# Peripherals.net
KiCad netlist of a schematic drawn in EAGLE
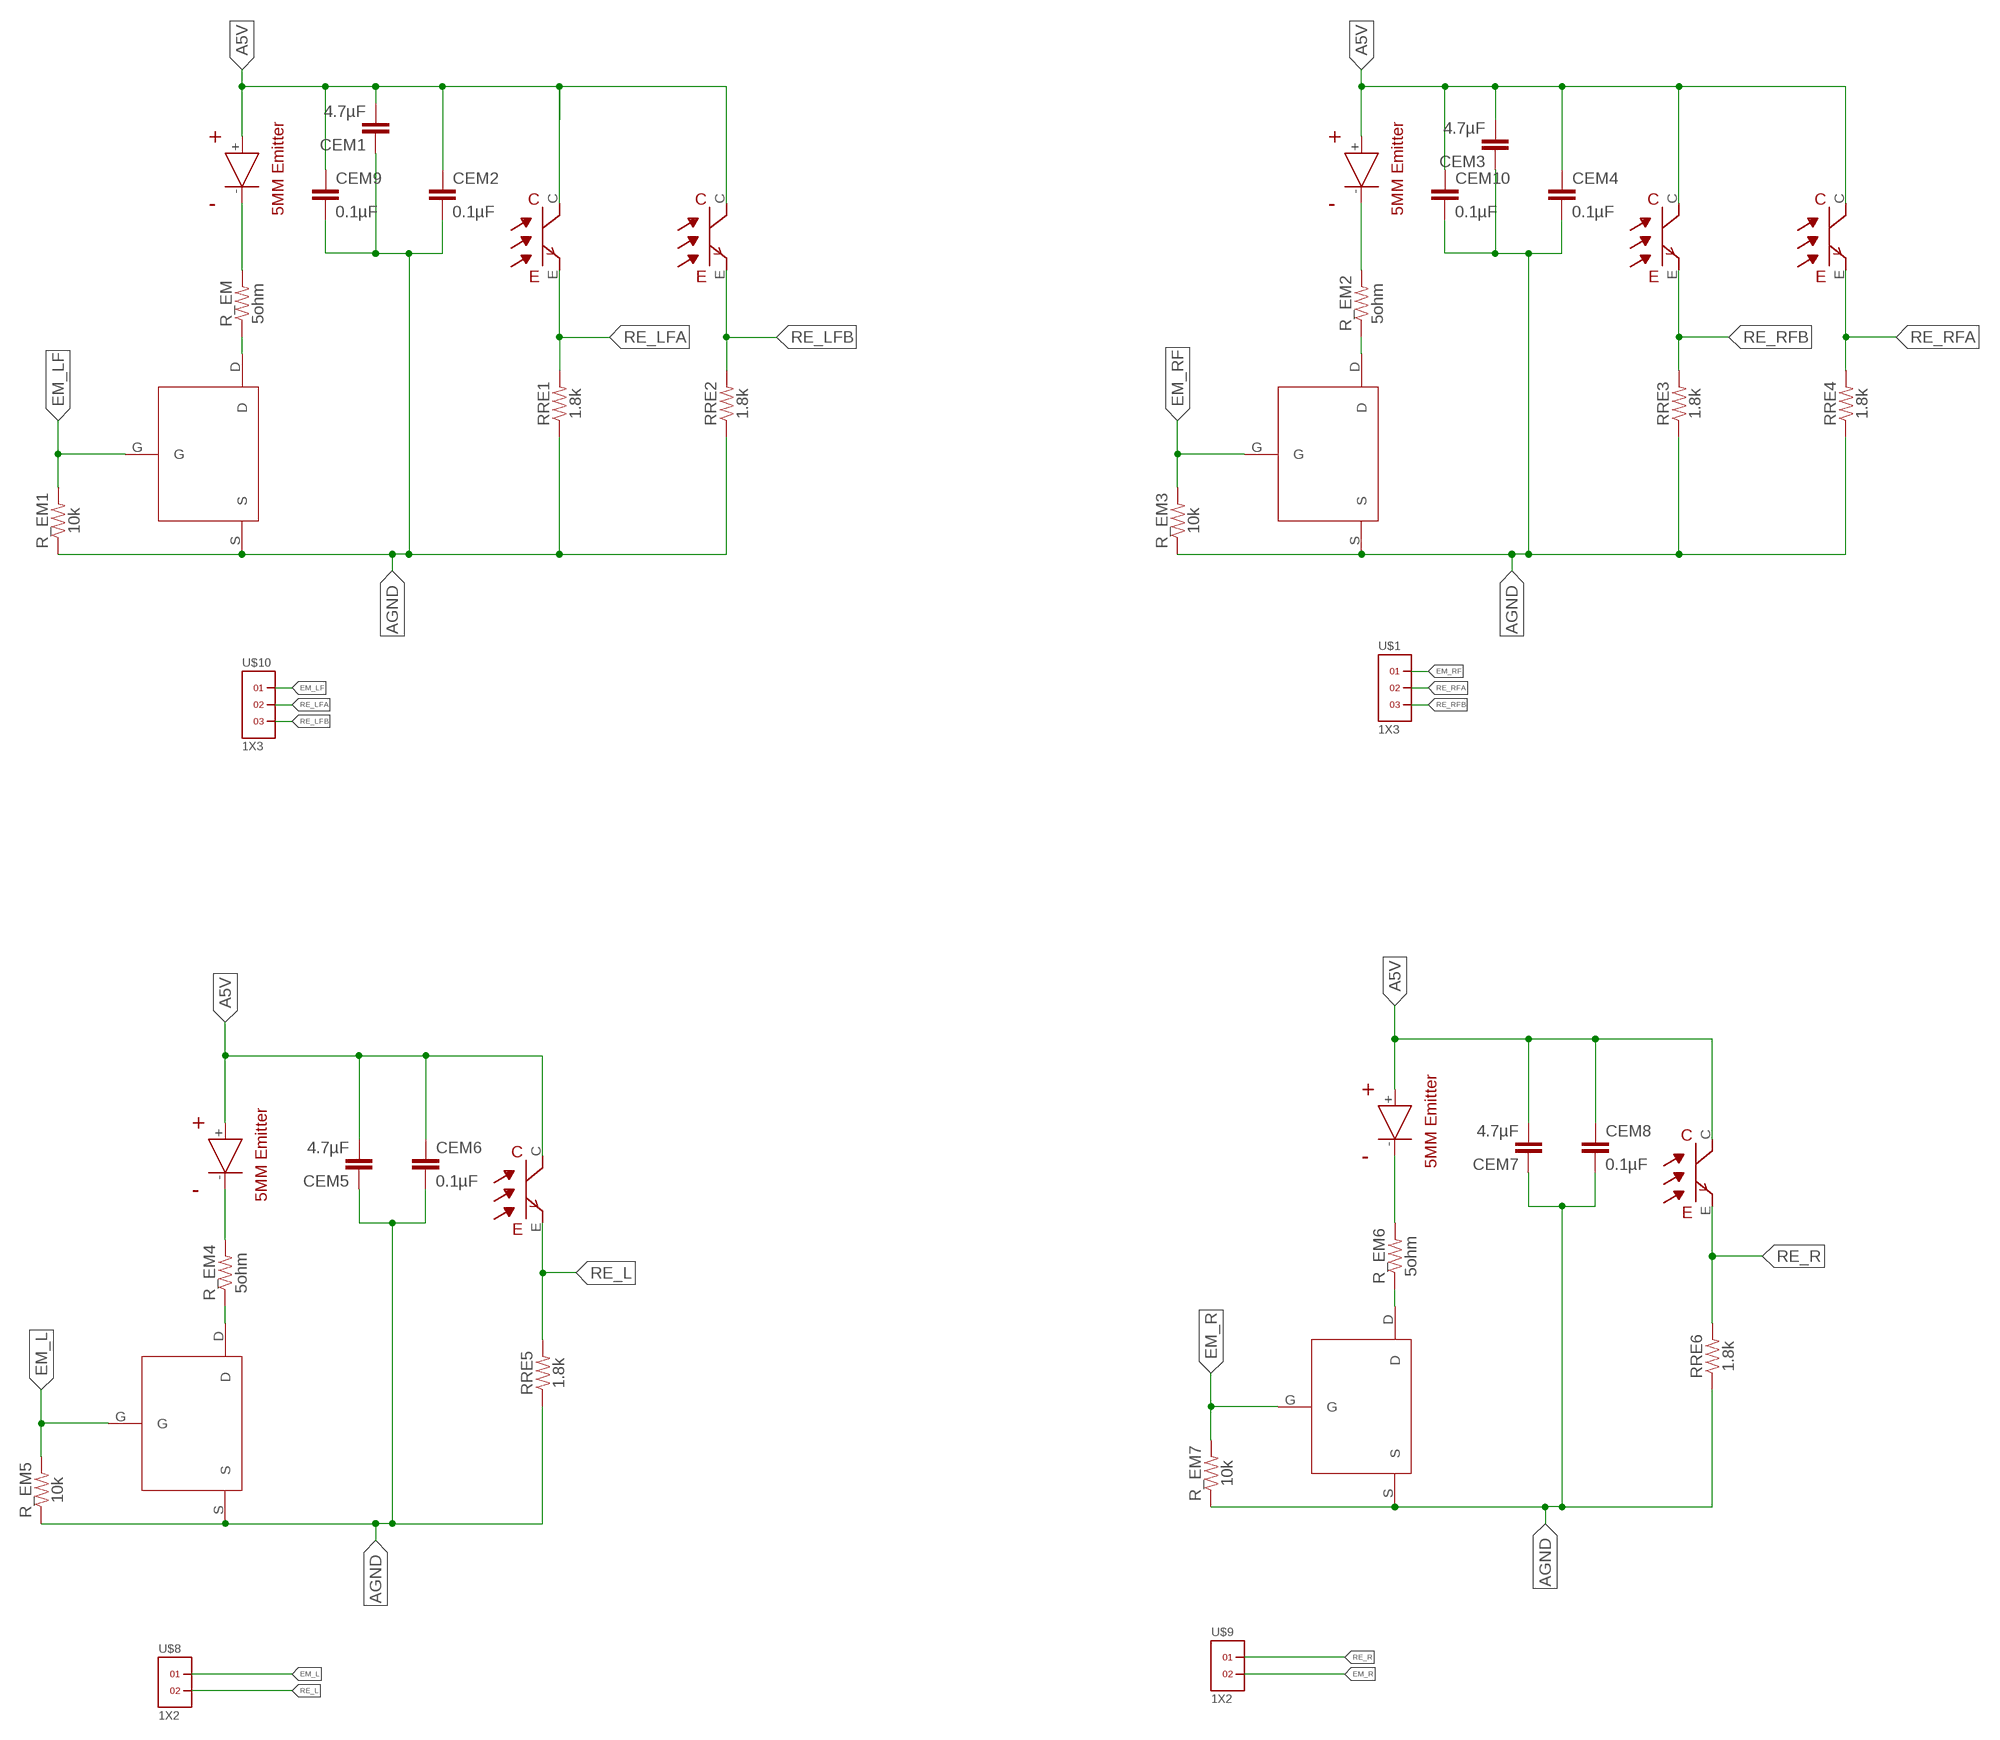
[diagram p0: schematic, sheet 1, part 1 of 2]
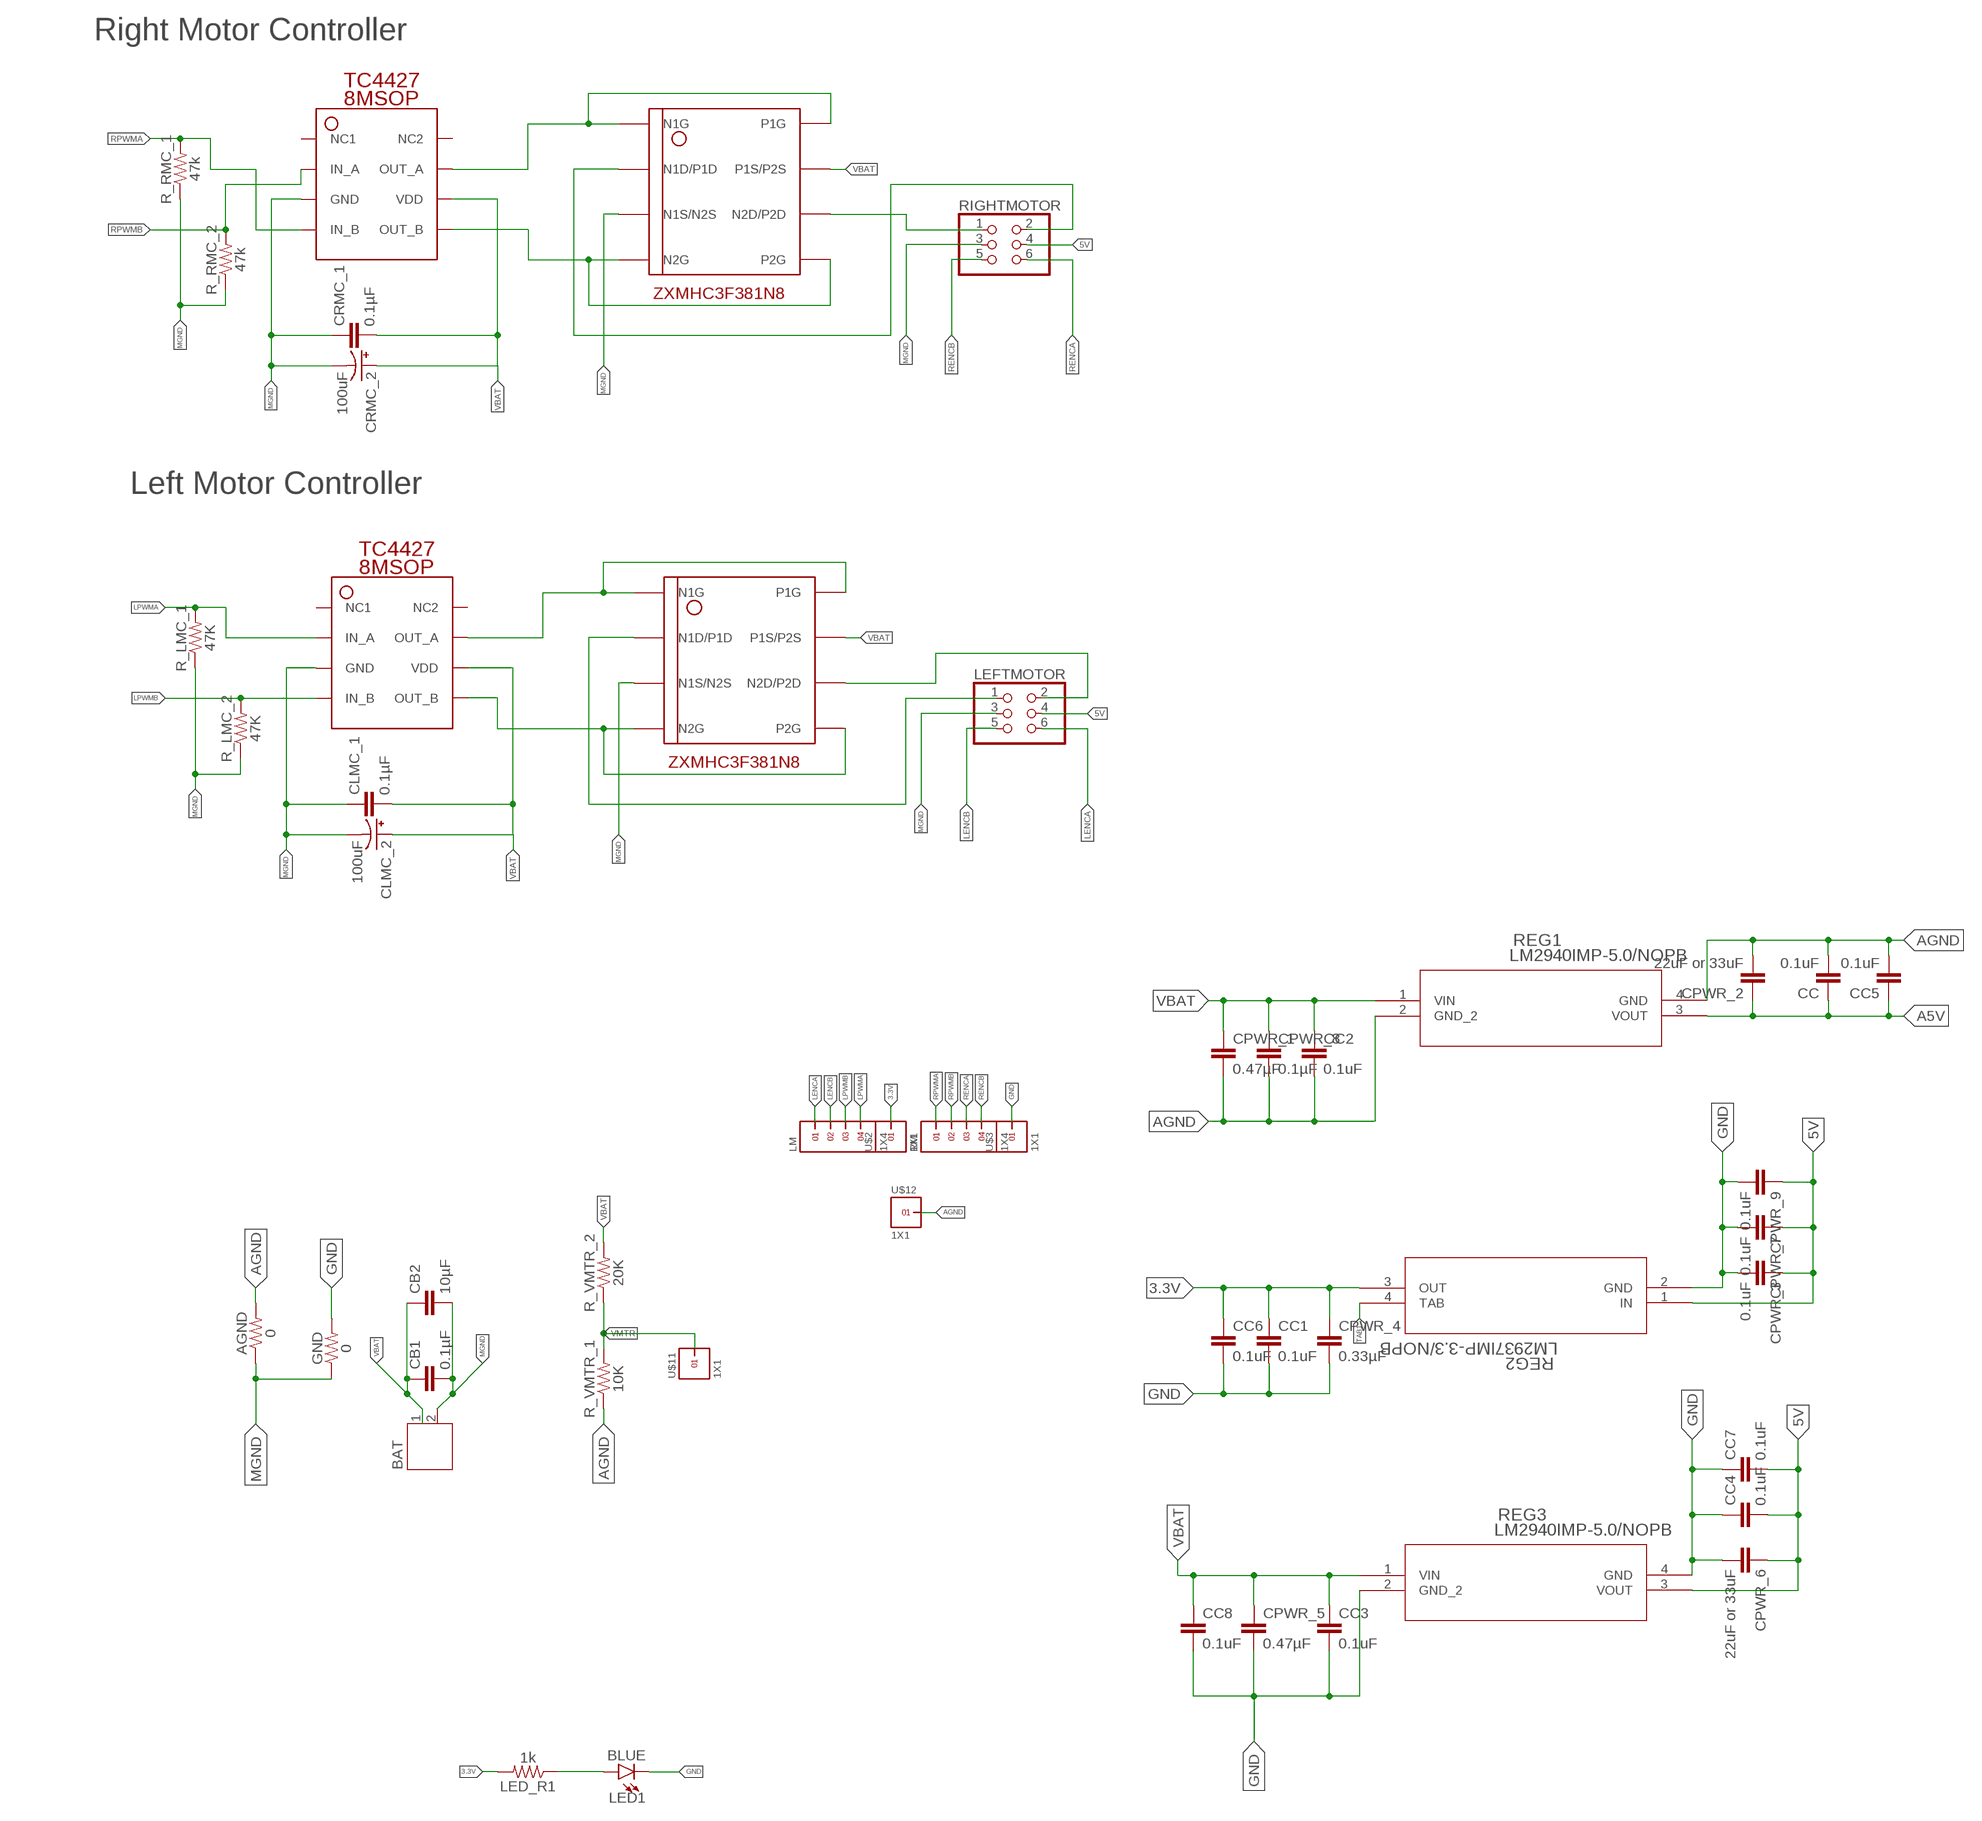
[diagram p1: schematic, sheet 1, part 2 of 2]

(export (version "E")
  (design (tool "Eeschema 10.0.6"))
  (components
    (comp (ref "AGND")
      (value "0")
      (footprint "eagle-import:0805")
      (libsource (lib "eagle-import") (part "SparkFun-Resistors_532_0.75OHM-0805-1/4W-1%"))
    )
    (comp (ref "BAT")
      (value "JST-PH2")
      (footprint "eagle-import:JST-PH2")
      (libsource (lib "eagle-import") (part "JST-PH2"))
    )
    (comp (ref "CB1")
      (value "0.1µF")
      (footprint "eagle-import:0805")
      (libsource (lib "eagle-import") (part "SparkFun-Capacitors_510_0.33UF/330NF-0805-50V-10%"))
    )
    (comp (ref "CB2")
      (value "10µF")
      (footprint "eagle-import:0805")
      (libsource (lib "eagle-import") (part "SparkFun-Capacitors_510_0.33UF/330NF-0805-50V-10%"))
    )
    (comp (ref "CC")
      (value "0.1uF")
      (footprint "eagle-import:0805")
      (libsource (lib "eagle-import") (part "0.33UF/330NF-0805-50V-10%"))
    )
    (comp (ref "CC1")
      (value "0.1uF")
      (footprint "eagle-import:0805")
      (libsource (lib "eagle-import") (part "0.33UF/330NF-0805-50V-10%"))
    )
    (comp (ref "CC2")
      (value "0.1uF")
      (footprint "eagle-import:0805")
      (libsource (lib "eagle-import") (part "0.33UF/330NF-0805-50V-10%"))
    )
    (comp (ref "CC3")
      (value "0.1uF")
      (footprint "eagle-import:0805")
      (libsource (lib "eagle-import") (part "0.33UF/330NF-0805-50V-10%"))
    )
    (comp (ref "CC4")
      (value "0.1uF")
      (footprint "eagle-import:0805")
      (libsource (lib "eagle-import") (part "0.33UF/330NF-0805-50V-10%"))
    )
    (comp (ref "CC5")
      (value "0.1uF")
      (footprint "eagle-import:0805")
      (libsource (lib "eagle-import") (part "0.33UF/330NF-0805-50V-10%"))
    )
    (comp (ref "CC6")
      (value "0.1uF")
      (footprint "eagle-import:0805")
      (libsource (lib "eagle-import") (part "0.33UF/330NF-0805-50V-10%"))
    )
    (comp (ref "CC7")
      (value "0.1uF")
      (footprint "eagle-import:0805")
      (libsource (lib "eagle-import") (part "0.33UF/330NF-0805-50V-10%"))
    )
    (comp (ref "CC8")
      (value "0.1uF")
      (footprint "eagle-import:0805")
      (libsource (lib "eagle-import") (part "0.33UF/330NF-0805-50V-10%"))
    )
    (comp (ref "CEM1")
      (value "4.7µF")
      (footprint "eagle-import:0805")
      (libsource (lib "eagle-import") (part "0.33UF/330NF-0805-50V-10%"))
    )
    (comp (ref "CEM2")
      (value "0.1µF")
      (footprint "eagle-import:0805")
      (libsource (lib "eagle-import") (part "0.33UF/330NF-0805-50V-10%"))
    )
    (comp (ref "CEM3")
      (value "4.7µF")
      (footprint "eagle-import:0805")
      (libsource (lib "eagle-import") (part "0.33UF/330NF-0805-50V-10%"))
    )
    (comp (ref "CEM4")
      (value "0.1µF")
      (footprint "eagle-import:0805")
      (libsource (lib "eagle-import") (part "0.33UF/330NF-0805-50V-10%"))
    )
    (comp (ref "CEM5")
      (value "4.7µF")
      (footprint "eagle-import:0805")
      (libsource (lib "eagle-import") (part "0.33UF/330NF-0805-50V-10%"))
    )
    (comp (ref "CEM6")
      (value "0.1µF")
      (footprint "eagle-import:0805")
      (libsource (lib "eagle-import") (part "0.33UF/330NF-0805-50V-10%"))
    )
    (comp (ref "CEM7")
      (value "4.7µF")
      (footprint "eagle-import:0805")
      (libsource (lib "eagle-import") (part "0.33UF/330NF-0805-50V-10%"))
    )
    (comp (ref "CEM8")
      (value "0.1µF")
      (footprint "eagle-import:0805")
      (libsource (lib "eagle-import") (part "0.33UF/330NF-0805-50V-10%"))
    )
    (comp (ref "CEM9")
      (value "0.1µF")
      (footprint "eagle-import:0805")
      (libsource (lib "eagle-import") (part "0.33UF/330NF-0805-50V-10%"))
    )
    (comp (ref "CEM10")
      (value "0.1µF")
      (footprint "eagle-import:0805")
      (libsource (lib "eagle-import") (part "0.33UF/330NF-0805-50V-10%"))
    )
    (comp (ref "CLMC_1")
      (value "0.1µF")
      (footprint "eagle-import:0805")
      (libsource (lib "eagle-import") (part "SparkFun-Capacitors_510_0.33UF/330NF-0805-50V-10%"))
    )
    (comp (ref "CLMC_2")
      (value "100uF")
      (footprint "eagle-import:EIA7343")
      (libsource (lib "eagle-import") (part "100UF-POLAR-EIA7343-10V-10%(TANT)"))
    )
    (comp (ref "CPWR_1")
      (value "0.47µF")
      (footprint "eagle-import:0805")
      (libsource (lib "eagle-import") (part "0.33UF/330NF-0805-50V-10%"))
    )
    (comp (ref "CPWR_2")
      (value "22uF or 33uF")
      (footprint "eagle-import:0805")
      (libsource (lib "eagle-import") (part "0.33UF/330NF-0805-50V-10%"))
    )
    (comp (ref "CPWR_3")
      (value "0.1uF")
      (footprint "eagle-import:0805")
      (libsource (lib "eagle-import") (part "0.33UF/330NF-0805-50V-10%"))
    )
    (comp (ref "CPWR_4")
      (value "0.33µF")
      (footprint "eagle-import:0805")
      (libsource (lib "eagle-import") (part "0.33UF/330NF-0805-50V-10%"))
    )
    (comp (ref "CPWR_5")
      (value "0.47µF")
      (footprint "eagle-import:0805")
      (libsource (lib "eagle-import") (part "0.33UF/330NF-0805-50V-10%"))
    )
    (comp (ref "CPWR_6")
      (value "22uF or 33uF")
      (footprint "eagle-import:0805")
      (libsource (lib "eagle-import") (part "0.33UF/330NF-0805-50V-10%"))
    )
    (comp (ref "CPWR_7")
      (value "0.1uF")
      (footprint "eagle-import:0805")
      (libsource (lib "eagle-import") (part "0.33UF/330NF-0805-50V-10%"))
    )
    (comp (ref "CPWR_8")
      (value "0.1µF")
      (footprint "eagle-import:0805")
      (libsource (lib "eagle-import") (part "0.33UF/330NF-0805-50V-10%"))
    )
    (comp (ref "CPWR_9")
      (value "0.1uF")
      (footprint "eagle-import:0805")
      (libsource (lib "eagle-import") (part "0.33UF/330NF-0805-50V-10%"))
    )
    (comp (ref "CRMC_1")
      (value "0.1µF")
      (footprint "eagle-import:0805")
      (libsource (lib "eagle-import") (part "SparkFun-Capacitors_510_0.33UF/330NF-0805-50V-10%"))
    )
    (comp (ref "CRMC_2")
      (value "100uF")
      (footprint "eagle-import:EIA7343")
      (libsource (lib "eagle-import") (part "100UF-POLAR-EIA7343-10V-10%(TANT)"))
    )
    (comp (ref "EM_L")
      (value "EMITTER")
      (footprint "eagle-import:EMITTER")
      (libsource (lib "eagle-import") (part "EMITTER"))
    )
    (comp (ref "EM_LF")
      (value "EMITTER")
      (footprint "eagle-import:EMITTER")
      (libsource (lib "eagle-import") (part "EMITTER"))
    )
    (comp (ref "EM_R")
      (value "EMITTER")
      (footprint "eagle-import:EMITTER")
      (libsource (lib "eagle-import") (part "EMITTER"))
    )
    (comp (ref "EM_RF")
      (value "EMITTER")
      (footprint "eagle-import:EMITTER")
      (libsource (lib "eagle-import") (part "EMITTER"))
    )
    (comp (ref "GND")
      (value "0")
      (footprint "eagle-import:0805")
      (libsource (lib "eagle-import") (part "SparkFun-Resistors_532_0.75OHM-0805-1/4W-1%"))
    )
    (comp (ref "LED1")
      (value "BLUE")
      (footprint "eagle-import:LED-1206")
      (libsource (lib "eagle-import") (part "LED-BLUE1206"))
    )
    (comp (ref "LED_R1")
      (value "1k")
      (footprint "eagle-import:0805")
      (libsource (lib "eagle-import") (part "0.75OHM-0805-1/4W-1%"))
    )
    (comp (ref "LEFTMOTOR")
      (value "PINHD-2X3")
      (footprint "eagle-import:2X03")
      (libsource (lib "eagle-import") (part "PINHD-2X3"))
    )
    (comp (ref "LM")
      (value "1X4")
      (footprint "eagle-import:1X4")
      (libsource (lib "eagle-import") (part "1X4"))
    )
    (comp (ref "REG1")
      (value "LM2940IMP-5.0/NOPB")
      (footprint "eagle-import:MP04A")
      (fields
        (field (name "MANUFACTURER_PART_NUMBER") "LM2940IMP5.0NOPB")
        (field (name "COPYRIGHT") "Copyright C 2015 Accelerated Designs. All rights reserved")
      )
      (libsource (lib "eagle-import") (part "LM2940IMP-5.0/NOPB"))
    )
    (comp (ref "REG2")
      (value "LM2937IMP-3.3/NOPB")
      (footprint "eagle-import:MP04A")
      (fields
        (field (name "MANUFACTURER_PART_NUMBER") "lm2937imp3_3nopb")
        (field (name "COPYRIGHT") "Copyright C 2015 Accelerated Designs. All rights reserved")
      )
      (libsource (lib "eagle-import") (part "LM2937IMP-3.3/NOPB"))
    )
    (comp (ref "REG3")
      (value "LM2940IMP-5.0/NOPB")
      (footprint "eagle-import:MP04A")
      (fields
        (field (name "MANUFACTURER_PART_NUMBER") "LM2940IMP5.0NOPB")
        (field (name "COPYRIGHT") "Copyright C 2015 Accelerated Designs. All rights reserved")
      )
      (libsource (lib "eagle-import") (part "LM2940IMP-5.0/NOPB"))
    )
    (comp (ref "RE_L")
      (value "RECEIVER")
      (footprint "eagle-import:RECEIVER")
      (libsource (lib "eagle-import") (part "RECEIVER"))
    )
    (comp (ref "RE_LFA")
      (value "RECEIVER")
      (footprint "eagle-import:RECEIVER")
      (libsource (lib "eagle-import") (part "RECEIVER"))
    )
    (comp (ref "RE_LFB")
      (value "RECEIVER")
      (footprint "eagle-import:RECEIVER")
      (libsource (lib "eagle-import") (part "RECEIVER"))
    )
    (comp (ref "RE_R")
      (value "RECEIVER")
      (footprint "eagle-import:RECEIVER")
      (libsource (lib "eagle-import") (part "RECEIVER"))
    )
    (comp (ref "RE_RFA")
      (value "RECEIVER")
      (footprint "eagle-import:RECEIVER")
      (libsource (lib "eagle-import") (part "RECEIVER"))
    )
    (comp (ref "RE_RFB")
      (value "RECEIVER")
      (footprint "eagle-import:RECEIVER")
      (libsource (lib "eagle-import") (part "RECEIVER"))
    )
    (comp (ref "RIGHTMOTOR")
      (value "PINHD-2X3")
      (footprint "eagle-import:2X03")
      (libsource (lib "eagle-import") (part "PINHD-2X3"))
    )
    (comp (ref "RM")
      (value "1X4")
      (footprint "eagle-import:1X4")
      (libsource (lib "eagle-import") (part "1X4"))
    )
    (comp (ref "RRE1")
      (value "1.8k")
      (footprint "eagle-import:0805")
      (libsource (lib "eagle-import") (part "0.75OHM-0805-1/4W-1%"))
    )
    (comp (ref "RRE2")
      (value "1.8k")
      (footprint "eagle-import:0805")
      (libsource (lib "eagle-import") (part "0.75OHM-0805-1/4W-1%"))
    )
    (comp (ref "RRE3")
      (value "1.8k")
      (footprint "eagle-import:0805")
      (libsource (lib "eagle-import") (part "0.75OHM-0805-1/4W-1%"))
    )
    (comp (ref "RRE4")
      (value "1.8k")
      (footprint "eagle-import:0805")
      (libsource (lib "eagle-import") (part "0.75OHM-0805-1/4W-1%"))
    )
    (comp (ref "RRE5")
      (value "1.8k")
      (footprint "eagle-import:0805")
      (libsource (lib "eagle-import") (part "0.75OHM-0805-1/4W-1%"))
    )
    (comp (ref "RRE6")
      (value "1.8k")
      (footprint "eagle-import:0805")
      (libsource (lib "eagle-import") (part "0.75OHM-0805-1/4W-1%"))
    )
    (comp (ref "R_EM")
      (value "5ohm")
      (footprint "eagle-import:0805")
      (libsource (lib "eagle-import") (part "0.75OHM-0805-1/4W-1%"))
    )
    (comp (ref "R_EM1")
      (value "10k")
      (footprint "eagle-import:0805")
      (libsource (lib "eagle-import") (part "0.75OHM-0805-1/4W-1%"))
    )
    (comp (ref "R_EM2")
      (value "5ohm")
      (footprint "eagle-import:0805")
      (libsource (lib "eagle-import") (part "0.75OHM-0805-1/4W-1%"))
    )
    (comp (ref "R_EM3")
      (value "10k")
      (footprint "eagle-import:0805")
      (libsource (lib "eagle-import") (part "0.75OHM-0805-1/4W-1%"))
    )
    (comp (ref "R_EM4")
      (value "5ohm")
      (footprint "eagle-import:0805")
      (libsource (lib "eagle-import") (part "0.75OHM-0805-1/4W-1%"))
    )
    (comp (ref "R_EM5")
      (value "10k")
      (footprint "eagle-import:0805")
      (libsource (lib "eagle-import") (part "0.75OHM-0805-1/4W-1%"))
    )
    (comp (ref "R_EM6")
      (value "5ohm")
      (footprint "eagle-import:0805")
      (libsource (lib "eagle-import") (part "0.75OHM-0805-1/4W-1%"))
    )
    (comp (ref "R_EM7")
      (value "10k")
      (footprint "eagle-import:0805")
      (libsource (lib "eagle-import") (part "0.75OHM-0805-1/4W-1%"))
    )
    (comp (ref "R_LMC_1")
      (value "47K")
      (footprint "eagle-import:0805")
      (libsource (lib "eagle-import") (part "SparkFun-Resistors_532_0.75OHM-0805-1/4W-1%"))
    )
    (comp (ref "R_LMC_2")
      (value "47K")
      (footprint "eagle-import:0805")
      (libsource (lib "eagle-import") (part "SparkFun-Resistors_532_0.75OHM-0805-1/4W-1%"))
    )
    (comp (ref "R_RMC_1")
      (value "47k")
      (footprint "eagle-import:0805")
      (libsource (lib "eagle-import") (part "SparkFun-Resistors_532_0.75OHM-0805-1/4W-1%"))
    )
    (comp (ref "R_RMC_2")
      (value "47k")
      (footprint "eagle-import:0805")
      (libsource (lib "eagle-import") (part "SparkFun-Resistors_532_0.75OHM-0805-1/4W-1%"))
    )
    (comp (ref "R_VMTR_1")
      (value "10K")
      (footprint "eagle-import:0805")
      (libsource (lib "eagle-import") (part "0.75OHM-0805-1/4W-1%"))
    )
    (comp (ref "R_VMTR_2")
      (value "20K")
      (footprint "eagle-import:0805")
      (libsource (lib "eagle-import") (part "0.75OHM-0805-1/4W-1%"))
    )
    (comp (ref "U$1")
      (value "1X3")
      (footprint "eagle-import:1X3")
      (libsource (lib "eagle-import") (part "1X3"))
    )
    (comp (ref "U$2")
      (value "1X1")
      (footprint "eagle-import:1X1")
      (libsource (lib "eagle-import") (part "1X1"))
    )
    (comp (ref "U$3")
      (value "1X1")
      (footprint "eagle-import:1X1")
      (libsource (lib "eagle-import") (part "1X1"))
    )
    (comp (ref "U$4")
      (value "MCH3474")
      (footprint "eagle-import:MCH3474")
      (libsource (lib "eagle-import") (part "MCH3474"))
    )
    (comp (ref "U$5")
      (value "MCH3474")
      (footprint "eagle-import:MCH3474")
      (libsource (lib "eagle-import") (part "MCH3474"))
    )
    (comp (ref "U$6")
      (value "MCH3474")
      (footprint "eagle-import:MCH3474")
      (libsource (lib "eagle-import") (part "MCH3474"))
    )
    (comp (ref "U$7")
      (value "MCH3474")
      (footprint "eagle-import:MCH3474")
      (libsource (lib "eagle-import") (part "MCH3474"))
    )
    (comp (ref "U$8")
      (value "1X2")
      (footprint "eagle-import:1X2")
      (libsource (lib "eagle-import") (part "1X2"))
    )
    (comp (ref "U$9")
      (value "1X2")
      (footprint "eagle-import:1X2")
      (libsource (lib "eagle-import") (part "1X2"))
    )
    (comp (ref "U$10")
      (value "1X3")
      (footprint "eagle-import:1X3")
      (libsource (lib "eagle-import") (part "1X3"))
    )
    (comp (ref "U$11")
      (value "1X1")
      (footprint "eagle-import:1X1")
      (libsource (lib "eagle-import") (part "1X1"))
    )
    (comp (ref "U$12")
      (value "1X1")
      (footprint "eagle-import:1X1")
      (libsource (lib "eagle-import") (part "1X1"))
    )
    (comp (ref "U$15")
      (value "TC4427(8MSOP)")
      (footprint "eagle-import:TC4427(8MSOP)")
      (libsource (lib "eagle-import") (part "TC4427(8MSOP)"))
    )
    (comp (ref "U$16")
      (value "ZXMHC3F381N8")
      (footprint "eagle-import:ZXMHC3F381N8")
      (libsource (lib "eagle-import") (part "ZXMHC3F381N8"))
    )
    (comp (ref "U$17")
      (value "TC4427(8MSOP)")
      (footprint "eagle-import:TC4427(8MSOP)")
      (libsource (lib "eagle-import") (part "TC4427(8MSOP)"))
    )
    (comp (ref "U$18")
      (value "ZXMHC3F381N8")
      (footprint "eagle-import:ZXMHC3F381N8")
      (libsource (lib "eagle-import") (part "ZXMHC3F381N8"))
    )
  )
  (nets
    (net (code "1") (name "3.3V") (class "Default")
      (node (ref "CC1") (pin "1") (pinfunction "1_1") (pintype "passive"))
      (node (ref "CC6") (pin "1") (pinfunction "1_1") (pintype "passive"))
      (node (ref "CPWR_4") (pin "1") (pinfunction "1_1") (pintype "passive"))
      (node (ref "LED_R1") (pin "2") (pinfunction "2_2") (pintype "passive"))
      (node (ref "REG2") (pin "3") (pinfunction "OUT_3") (pintype "power_in"))
      (node (ref "U$2") (pin "1") (pinfunction "1_1") (pintype "bidirectional"))
    )
    (net (code "2") (name "5V") (class "Default")
      (node (ref "CC4") (pin "2") (pinfunction "2_2") (pintype "passive"))
      (node (ref "CC7") (pin "2") (pinfunction "2_2") (pintype "passive"))
      (node (ref "CPWR_3") (pin "1") (pinfunction "1_1") (pintype "passive"))
      (node (ref "CPWR_6") (pin "1") (pinfunction "1_1") (pintype "passive"))
      (node (ref "CPWR_7") (pin "1") (pinfunction "1_1") (pintype "passive"))
      (node (ref "CPWR_9") (pin "1") (pinfunction "1_1") (pintype "passive"))
      (node (ref "LEFTMOTOR") (pin "4") (pinfunction "4_4") (pintype "passive"))
      (node (ref "REG2") (pin "1") (pinfunction "IN_1") (pintype "power_in"))
      (node (ref "REG3") (pin "3") (pinfunction "VOUT_3") (pintype "output"))
      (node (ref "RIGHTMOTOR") (pin "4") (pinfunction "4_4") (pintype "passive"))
    )
    (net (code "3") (name "A5V") (class "Default")
      (node (ref "CC") (pin "1") (pinfunction "1_1") (pintype "passive"))
      (node (ref "CC5") (pin "1") (pinfunction "1_1") (pintype "passive"))
      (node (ref "CEM1") (pin "2") (pinfunction "2_2") (pintype "passive"))
      (node (ref "CEM10") (pin "1") (pinfunction "1_1") (pintype "passive"))
      (node (ref "CEM2") (pin "1") (pinfunction "1_1") (pintype "passive"))
      (node (ref "CEM3") (pin "2") (pinfunction "2_2") (pintype "passive"))
      (node (ref "CEM4") (pin "1") (pinfunction "1_1") (pintype "passive"))
      (node (ref "CEM5") (pin "2") (pinfunction "2_2") (pintype "passive"))
      (node (ref "CEM6") (pin "1") (pinfunction "1_1") (pintype "passive"))
      (node (ref "CEM7") (pin "2") (pinfunction "2_2") (pintype "passive"))
      (node (ref "CEM8") (pin "1") (pinfunction "1_1") (pintype "passive"))
      (node (ref "CEM9") (pin "1") (pinfunction "1_1") (pintype "passive"))
      (node (ref "CPWR_2") (pin "1") (pinfunction "1_1") (pintype "passive"))
      (node (ref "EM_L") (pin "+") (pinfunction "+_+") (pintype "bidirectional"))
      (node (ref "EM_LF") (pin "+") (pinfunction "+_+") (pintype "bidirectional"))
      (node (ref "EM_R") (pin "+") (pinfunction "+_+") (pintype "bidirectional"))
      (node (ref "EM_RF") (pin "+") (pinfunction "+_+") (pintype "bidirectional"))
      (node (ref "REG1") (pin "3") (pinfunction "VOUT_3") (pintype "output"))
      (node (ref "RE_L") (pin "C") (pinfunction "C_C") (pintype "bidirectional"))
      (node (ref "RE_LFA") (pin "C") (pinfunction "C_C") (pintype "bidirectional"))
      (node (ref "RE_LFB") (pin "C") (pinfunction "C_C") (pintype "bidirectional"))
      (node (ref "RE_R") (pin "C") (pinfunction "C_C") (pintype "bidirectional"))
      (node (ref "RE_RFA") (pin "C") (pinfunction "C_C") (pintype "bidirectional"))
      (node (ref "RE_RFB") (pin "C") (pinfunction "C_C") (pintype "bidirectional"))
    )
    (net (code "4") (name "AGND") (class "Default")
      (node (ref "AGND") (pin "2") (pinfunction "2_2") (pintype "passive"))
      (node (ref "CC") (pin "2") (pinfunction "2_2") (pintype "passive"))
      (node (ref "CC2") (pin "2") (pinfunction "2_2") (pintype "passive"))
      (node (ref "CC5") (pin "2") (pinfunction "2_2") (pintype "passive"))
      (node (ref "CEM1") (pin "1") (pinfunction "1_1") (pintype "passive"))
      (node (ref "CEM10") (pin "2") (pinfunction "2_2") (pintype "passive"))
      (node (ref "CEM2") (pin "2") (pinfunction "2_2") (pintype "passive"))
      (node (ref "CEM3") (pin "1") (pinfunction "1_1") (pintype "passive"))
      (node (ref "CEM4") (pin "2") (pinfunction "2_2") (pintype "passive"))
      (node (ref "CEM5") (pin "1") (pinfunction "1_1") (pintype "passive"))
      (node (ref "CEM6") (pin "2") (pinfunction "2_2") (pintype "passive"))
      (node (ref "CEM7") (pin "1") (pinfunction "1_1") (pintype "passive"))
      (node (ref "CEM8") (pin "2") (pinfunction "2_2") (pintype "passive"))
      (node (ref "CEM9") (pin "2") (pinfunction "2_2") (pintype "passive"))
      (node (ref "CPWR_1") (pin "2") (pinfunction "2_2") (pintype "passive"))
      (node (ref "CPWR_2") (pin "2") (pinfunction "2_2") (pintype "passive"))
      (node (ref "CPWR_8") (pin "2") (pinfunction "2_2") (pintype "passive"))
      (node (ref "REG1") (pin "2") (pinfunction "GND_2_2") (pintype "power_in"))
      (node (ref "REG1") (pin "4") (pinfunction "GND_4") (pintype "power_in"))
      (node (ref "RRE1") (pin "1") (pinfunction "1_1") (pintype "passive"))
      (node (ref "RRE2") (pin "1") (pinfunction "1_1") (pintype "passive"))
      (node (ref "RRE3") (pin "1") (pinfunction "1_1") (pintype "passive"))
      (node (ref "RRE4") (pin "1") (pinfunction "1_1") (pintype "passive"))
      (node (ref "RRE5") (pin "1") (pinfunction "1_1") (pintype "passive"))
      (node (ref "RRE6") (pin "1") (pinfunction "1_1") (pintype "passive"))
      (node (ref "R_EM1") (pin "1") (pinfunction "1_1") (pintype "passive"))
      (node (ref "R_EM3") (pin "1") (pinfunction "1_1") (pintype "passive"))
      (node (ref "R_EM5") (pin "1") (pinfunction "1_1") (pintype "passive"))
      (node (ref "R_EM7") (pin "1") (pinfunction "1_1") (pintype "passive"))
      (node (ref "R_VMTR_1") (pin "1") (pinfunction "1_1") (pintype "passive"))
      (node (ref "U$12") (pin "1") (pinfunction "1_1") (pintype "bidirectional"))
      (node (ref "U$4") (pin "S") (pinfunction "S_S") (pintype "bidirectional"))
      (node (ref "U$5") (pin "S") (pinfunction "S_S") (pintype "bidirectional"))
      (node (ref "U$6") (pin "S") (pinfunction "S_S") (pintype "bidirectional"))
      (node (ref "U$7") (pin "S") (pinfunction "S_S") (pintype "bidirectional"))
    )
    (net (code "5") (name "EM_L") (class "Default")
      (node (ref "R_EM5") (pin "2") (pinfunction "2_2") (pintype "passive"))
      (node (ref "U$4") (pin "G") (pinfunction "G_G") (pintype "bidirectional"))
      (node (ref "U$8") (pin "1") (pinfunction "1_1") (pintype "bidirectional"))
    )
    (net (code "6") (name "EM_LF") (class "Default")
      (node (ref "R_EM1") (pin "2") (pinfunction "2_2") (pintype "passive"))
      (node (ref "U$10") (pin "1") (pinfunction "1_1") (pintype "bidirectional"))
      (node (ref "U$5") (pin "G") (pinfunction "G_G") (pintype "bidirectional"))
    )
    (net (code "7") (name "EM_R") (class "Default")
      (node (ref "R_EM7") (pin "2") (pinfunction "2_2") (pintype "passive"))
      (node (ref "U$7") (pin "G") (pinfunction "G_G") (pintype "bidirectional"))
      (node (ref "U$9") (pin "2") (pinfunction "2_2") (pintype "bidirectional"))
    )
    (net (code "8") (name "EM_RF") (class "Default")
      (node (ref "R_EM3") (pin "2") (pinfunction "2_2") (pintype "passive"))
      (node (ref "U$1") (pin "1") (pinfunction "1_1") (pintype "bidirectional"))
      (node (ref "U$6") (pin "G") (pinfunction "G_G") (pintype "bidirectional"))
    )
    (net (code "9") (name "GND") (class "Default")
      (node (ref "CC1") (pin "2") (pinfunction "2_2") (pintype "passive"))
      (node (ref "CC3") (pin "2") (pinfunction "2_2") (pintype "passive"))
      (node (ref "CC4") (pin "1") (pinfunction "1_1") (pintype "passive"))
      (node (ref "CC6") (pin "2") (pinfunction "2_2") (pintype "passive"))
      (node (ref "CC7") (pin "1") (pinfunction "1_1") (pintype "passive"))
      (node (ref "CC8") (pin "2") (pinfunction "2_2") (pintype "passive"))
      (node (ref "CPWR_3") (pin "2") (pinfunction "2_2") (pintype "passive"))
      (node (ref "CPWR_4") (pin "2") (pinfunction "2_2") (pintype "passive"))
      (node (ref "CPWR_5") (pin "2") (pinfunction "2_2") (pintype "passive"))
      (node (ref "CPWR_6") (pin "2") (pinfunction "2_2") (pintype "passive"))
      (node (ref "CPWR_7") (pin "2") (pinfunction "2_2") (pintype "passive"))
      (node (ref "CPWR_9") (pin "2") (pinfunction "2_2") (pintype "passive"))
      (node (ref "GND") (pin "2") (pinfunction "2_2") (pintype "passive"))
      (node (ref "LED1") (pin "C") (pinfunction "C_C") (pintype "passive"))
      (node (ref "REG2") (pin "2") (pinfunction "GND_2") (pintype "power_in"))
      (node (ref "REG3") (pin "2") (pinfunction "GND_2_2") (pintype "power_in"))
      (node (ref "REG3") (pin "4") (pinfunction "GND_4") (pintype "power_in"))
      (node (ref "U$3") (pin "1") (pinfunction "1_1") (pintype "bidirectional"))
    )
    (net (code "10") (name "LENCA") (class "Default")
      (node (ref "LEFTMOTOR") (pin "6") (pinfunction "6_6") (pintype "passive"))
      (node (ref "LM") (pin "1") (pinfunction "1_1") (pintype "bidirectional"))
    )
    (net (code "11") (name "LENCB") (class "Default")
      (node (ref "LEFTMOTOR") (pin "5") (pinfunction "5_5") (pintype "passive"))
      (node (ref "LM") (pin "2") (pinfunction "2_2") (pintype "bidirectional"))
    )
    (net (code "12") (name "LPWMA") (class "Default")
      (node (ref "LM") (pin "4") (pinfunction "4_4") (pintype "bidirectional"))
      (node (ref "R_LMC_1") (pin "2") (pinfunction "2_2") (pintype "passive"))
      (node (ref "U$15") (pin "IN_A") (pinfunction "IN_A_IN_A") (pintype "bidirectional"))
    )
    (net (code "13") (name "LPWMB") (class "Default")
      (node (ref "LM") (pin "3") (pinfunction "3_3") (pintype "bidirectional"))
      (node (ref "R_LMC_2") (pin "2") (pinfunction "2_2") (pintype "passive"))
      (node (ref "U$15") (pin "IN_B") (pinfunction "IN_B_IN_B") (pintype "bidirectional"))
    )
    (net (code "14") (name "MGND") (class "Default")
      (node (ref "AGND") (pin "1") (pinfunction "1_1") (pintype "passive"))
      (node (ref "BAT") (pin "2") (pinfunction "2_2") (pintype "passive"))
      (node (ref "CB1") (pin "2") (pinfunction "2_2") (pintype "passive"))
      (node (ref "CB2") (pin "2") (pinfunction "2_2") (pintype "passive"))
      (node (ref "CLMC_1") (pin "1") (pinfunction "1_1") (pintype "passive"))
      (node (ref "CLMC_2") (pin "C") (pinfunction "-_C") (pintype "passive"))
      (node (ref "CRMC_1") (pin "1") (pinfunction "1_1") (pintype "passive"))
      (node (ref "CRMC_2") (pin "C") (pinfunction "-_C") (pintype "passive"))
      (node (ref "GND") (pin "1") (pinfunction "1_1") (pintype "passive"))
      (node (ref "LEFTMOTOR") (pin "3") (pinfunction "3_3") (pintype "passive"))
      (node (ref "RIGHTMOTOR") (pin "3") (pinfunction "3_3") (pintype "passive"))
      (node (ref "R_LMC_1") (pin "1") (pinfunction "1_1") (pintype "passive"))
      (node (ref "R_LMC_2") (pin "1") (pinfunction "1_1") (pintype "passive"))
      (node (ref "R_RMC_1") (pin "1") (pinfunction "1_1") (pintype "passive"))
      (node (ref "R_RMC_2") (pin "1") (pinfunction "1_1") (pintype "passive"))
      (node (ref "U$15") (pin "GND") (pinfunction "GND_GND") (pintype "bidirectional"))
      (node (ref "U$16") (pin "N1S/N2S") (pinfunction "N1S/N2S_N1S/N2S") (pintype "bidirectional"))
      (node (ref "U$17") (pin "GND") (pinfunction "GND_GND") (pintype "bidirectional"))
      (node (ref "U$18") (pin "N1S/N2S") (pinfunction "N1S/N2S_N1S/N2S") (pintype "bidirectional"))
    )
    (net (code "15") (name "Net-(EM_L-Pad-)") (class "Default")
      (node (ref "EM_L") (pin "-") (pinfunction "-_-") (pintype "bidirectional"))
      (node (ref "R_EM4") (pin "2") (pinfunction "2_2") (pintype "passive"))
    )
    (net (code "16") (name "Net-(EM_LF-Pad-)") (class "Default")
      (node (ref "EM_LF") (pin "-") (pinfunction "-_-") (pintype "bidirectional"))
      (node (ref "R_EM") (pin "2") (pinfunction "2_2") (pintype "passive"))
    )
    (net (code "17") (name "Net-(EM_R-Pad-)") (class "Default")
      (node (ref "EM_R") (pin "-") (pinfunction "-_-") (pintype "bidirectional"))
      (node (ref "R_EM6") (pin "2") (pinfunction "2_2") (pintype "passive"))
    )
    (net (code "18") (name "Net-(EM_RF-Pad-)") (class "Default")
      (node (ref "EM_RF") (pin "-") (pinfunction "-_-") (pintype "bidirectional"))
      (node (ref "R_EM2") (pin "2") (pinfunction "2_2") (pintype "passive"))
    )
    (net (code "19") (name "Net-(LED1-PadA)") (class "Default")
      (node (ref "LED1") (pin "A") (pinfunction "A_A") (pintype "passive"))
      (node (ref "LED_R1") (pin "1") (pinfunction "1_1") (pintype "passive"))
    )
    (net (code "20") (name "Net-(LEFTMOTOR-Pad1)") (class "Default")
      (node (ref "LEFTMOTOR") (pin "1") (pinfunction "1_1") (pintype "passive"))
      (node (ref "U$16") (pin "N1D/P1D") (pinfunction "N1D/P1D_N1D/P1D") (pintype "bidirectional"))
    )
    (net (code "21") (name "Net-(LEFTMOTOR-Pad2)") (class "Default")
      (node (ref "LEFTMOTOR") (pin "2") (pinfunction "2_2") (pintype "passive"))
      (node (ref "U$16") (pin "N2D/P2D") (pinfunction "N2D/P2D_N2D/P2D") (pintype "bidirectional"))
    )
    (net (code "22") (name "Net-(RIGHTMOTOR-Pad1)") (class "Default")
      (node (ref "RIGHTMOTOR") (pin "1") (pinfunction "1_1") (pintype "passive"))
      (node (ref "U$18") (pin "N2D/P2D") (pinfunction "N2D/P2D_N2D/P2D") (pintype "bidirectional"))
    )
    (net (code "23") (name "Net-(RIGHTMOTOR-Pad2)") (class "Default")
      (node (ref "RIGHTMOTOR") (pin "2") (pinfunction "2_2") (pintype "passive"))
      (node (ref "U$18") (pin "N1D/P1D") (pinfunction "N1D/P1D_N1D/P1D") (pintype "bidirectional"))
    )
    (net (code "24") (name "Net-(R_EM-Pad1)") (class "Default")
      (node (ref "R_EM") (pin "1") (pinfunction "1_1") (pintype "passive"))
      (node (ref "U$5") (pin "D") (pinfunction "D_D") (pintype "bidirectional"))
    )
    (net (code "25") (name "Net-(R_EM2-Pad1)") (class "Default")
      (node (ref "R_EM2") (pin "1") (pinfunction "1_1") (pintype "passive"))
      (node (ref "U$6") (pin "D") (pinfunction "D_D") (pintype "bidirectional"))
    )
    (net (code "26") (name "Net-(R_EM4-Pad1)") (class "Default")
      (node (ref "R_EM4") (pin "1") (pinfunction "1_1") (pintype "passive"))
      (node (ref "U$4") (pin "D") (pinfunction "D_D") (pintype "bidirectional"))
    )
    (net (code "27") (name "Net-(R_EM6-Pad1)") (class "Default")
      (node (ref "R_EM6") (pin "1") (pinfunction "1_1") (pintype "passive"))
      (node (ref "U$7") (pin "D") (pinfunction "D_D") (pintype "bidirectional"))
    )
    (net (code "28") (name "Net-(U$15-PadOUT_A)") (class "Default")
      (node (ref "U$15") (pin "OUT_A") (pinfunction "OUT_A_OUT_A") (pintype "bidirectional"))
      (node (ref "U$16") (pin "N1G") (pinfunction "N1G_N1G") (pintype "bidirectional"))
      (node (ref "U$16") (pin "P1G") (pinfunction "P1G_P1G") (pintype "bidirectional"))
    )
    (net (code "29") (name "Net-(U$15-PadOUT_B)") (class "Default")
      (node (ref "U$15") (pin "OUT_B") (pinfunction "OUT_B_OUT_B") (pintype "bidirectional"))
      (node (ref "U$16") (pin "N2G") (pinfunction "N2G_N2G") (pintype "bidirectional"))
      (node (ref "U$16") (pin "P2G") (pinfunction "P2G_P2G") (pintype "bidirectional"))
    )
    (net (code "30") (name "Net-(U$17-PadOUT_A)") (class "Default")
      (node (ref "U$17") (pin "OUT_A") (pinfunction "OUT_A_OUT_A") (pintype "bidirectional"))
      (node (ref "U$18") (pin "N1G") (pinfunction "N1G_N1G") (pintype "bidirectional"))
      (node (ref "U$18") (pin "P1G") (pinfunction "P1G_P1G") (pintype "bidirectional"))
    )
    (net (code "31") (name "Net-(U$17-PadOUT_B)") (class "Default")
      (node (ref "U$17") (pin "OUT_B") (pinfunction "OUT_B_OUT_B") (pintype "bidirectional"))
      (node (ref "U$18") (pin "N2G") (pinfunction "N2G_N2G") (pintype "bidirectional"))
      (node (ref "U$18") (pin "P2G") (pinfunction "P2G_P2G") (pintype "bidirectional"))
    )
    (net (code "32") (name "RENCA") (class "Default")
      (node (ref "RIGHTMOTOR") (pin "6") (pinfunction "6_6") (pintype "passive"))
      (node (ref "RM") (pin "3") (pinfunction "3_3") (pintype "bidirectional"))
    )
    (net (code "33") (name "RENCB") (class "Default")
      (node (ref "RIGHTMOTOR") (pin "5") (pinfunction "5_5") (pintype "passive"))
      (node (ref "RM") (pin "4") (pinfunction "4_4") (pintype "bidirectional"))
    )
    (net (code "34") (name "RE_L") (class "Default")
      (node (ref "RE_L") (pin "E") (pinfunction "E_E") (pintype "bidirectional"))
      (node (ref "RRE5") (pin "2") (pinfunction "2_2") (pintype "passive"))
      (node (ref "U$8") (pin "2") (pinfunction "2_2") (pintype "bidirectional"))
    )
    (net (code "35") (name "RE_LFA") (class "Default")
      (node (ref "RE_LFA") (pin "E") (pinfunction "E_E") (pintype "bidirectional"))
      (node (ref "RRE1") (pin "2") (pinfunction "2_2") (pintype "passive"))
      (node (ref "U$10") (pin "2") (pinfunction "2_2") (pintype "bidirectional"))
    )
    (net (code "36") (name "RE_LFB") (class "Default")
      (node (ref "RE_LFB") (pin "E") (pinfunction "E_E") (pintype "bidirectional"))
      (node (ref "RRE2") (pin "2") (pinfunction "2_2") (pintype "passive"))
      (node (ref "U$10") (pin "3") (pinfunction "3_3") (pintype "bidirectional"))
    )
    (net (code "37") (name "RE_R") (class "Default")
      (node (ref "RE_R") (pin "E") (pinfunction "E_E") (pintype "bidirectional"))
      (node (ref "RRE6") (pin "2") (pinfunction "2_2") (pintype "passive"))
      (node (ref "U$9") (pin "1") (pinfunction "1_1") (pintype "bidirectional"))
    )
    (net (code "38") (name "RE_RFA") (class "Default")
      (node (ref "RE_RFB") (pin "E") (pinfunction "E_E") (pintype "bidirectional"))
      (node (ref "RRE4") (pin "2") (pinfunction "2_2") (pintype "passive"))
      (node (ref "U$1") (pin "2") (pinfunction "2_2") (pintype "bidirectional"))
    )
    (net (code "39") (name "RE_RFB") (class "Default")
      (node (ref "RE_RFA") (pin "E") (pinfunction "E_E") (pintype "bidirectional"))
      (node (ref "RRE3") (pin "2") (pinfunction "2_2") (pintype "passive"))
      (node (ref "U$1") (pin "3") (pinfunction "3_3") (pintype "bidirectional"))
    )
    (net (code "40") (name "RPWMA") (class "Default")
      (node (ref "RM") (pin "1") (pinfunction "1_1") (pintype "bidirectional"))
      (node (ref "R_RMC_1") (pin "2") (pinfunction "2_2") (pintype "passive"))
      (node (ref "U$17") (pin "IN_B") (pinfunction "IN_B_IN_B") (pintype "bidirectional"))
    )
    (net (code "41") (name "RPWMB") (class "Default")
      (node (ref "RM") (pin "2") (pinfunction "2_2") (pintype "bidirectional"))
      (node (ref "R_RMC_2") (pin "2") (pinfunction "2_2") (pintype "passive"))
      (node (ref "U$17") (pin "IN_A") (pinfunction "IN_A_IN_A") (pintype "bidirectional"))
    )
    (net (code "42") (name "TAB1") (class "Default")
      (node (ref "REG2") (pin "4") (pinfunction "TAB_4") (pintype "power_in"))
    )
    (net (code "43") (name "VBAT") (class "Default")
      (node (ref "BAT") (pin "1") (pinfunction "1_1") (pintype "passive"))
      (node (ref "CB1") (pin "1") (pinfunction "1_1") (pintype "passive"))
      (node (ref "CB2") (pin "1") (pinfunction "1_1") (pintype "passive"))
      (node (ref "CC2") (pin "1") (pinfunction "1_1") (pintype "passive"))
      (node (ref "CC3") (pin "1") (pinfunction "1_1") (pintype "passive"))
      (node (ref "CC8") (pin "1") (pinfunction "1_1") (pintype "passive"))
      (node (ref "CLMC_1") (pin "2") (pinfunction "2_2") (pintype "passive"))
      (node (ref "CLMC_2") (pin "A") (pinfunction "+_A") (pintype "passive"))
      (node (ref "CPWR_1") (pin "1") (pinfunction "1_1") (pintype "passive"))
      (node (ref "CPWR_5") (pin "1") (pinfunction "1_1") (pintype "passive"))
      (node (ref "CPWR_8") (pin "1") (pinfunction "1_1") (pintype "passive"))
      (node (ref "CRMC_1") (pin "2") (pinfunction "2_2") (pintype "passive"))
      (node (ref "CRMC_2") (pin "A") (pinfunction "+_A") (pintype "passive"))
      (node (ref "REG1") (pin "1") (pinfunction "VIN_1") (pintype "input"))
      (node (ref "REG3") (pin "1") (pinfunction "VIN_1") (pintype "input"))
      (node (ref "R_VMTR_2") (pin "2") (pinfunction "2_2") (pintype "passive"))
      (node (ref "U$15") (pin "VDD") (pinfunction "VDD_VDD") (pintype "bidirectional"))
      (node (ref "U$16") (pin "P1S/P2S") (pinfunction "P1S/P2S_P1S/P2S") (pintype "bidirectional"))
      (node (ref "U$17") (pin "VDD") (pinfunction "VDD_VDD") (pintype "bidirectional"))
      (node (ref "U$18") (pin "P1S/P2S") (pinfunction "P1S/P2S_P1S/P2S") (pintype "bidirectional"))
    )
    (net (code "44") (name "VMTR") (class "Default")
      (node (ref "R_VMTR_1") (pin "2") (pinfunction "2_2") (pintype "passive"))
      (node (ref "R_VMTR_2") (pin "1") (pinfunction "1_1") (pintype "passive"))
      (node (ref "U$11") (pin "1") (pinfunction "1_1") (pintype "bidirectional"))
    )
    (net (code "45") (name "unconnected-(U$15-PadNC1)") (class "Default")
      (node (ref "U$15") (pin "NC1") (pinfunction "NC1_NC1") (pintype "bidirectional"))
    )
    (net (code "46") (name "unconnected-(U$15-PadNC2)") (class "Default")
      (node (ref "U$15") (pin "NC2") (pinfunction "NC2_NC2") (pintype "bidirectional"))
    )
    (net (code "47") (name "unconnected-(U$17-PadNC1)") (class "Default")
      (node (ref "U$17") (pin "NC1") (pinfunction "NC1_NC1") (pintype "bidirectional"))
    )
    (net (code "48") (name "unconnected-(U$17-PadNC2)") (class "Default")
      (node (ref "U$17") (pin "NC2") (pinfunction "NC2_NC2") (pintype "bidirectional"))
    )
  )
)
